# spidmx.net
KiCad netlist of a schematic drawn in EAGLE
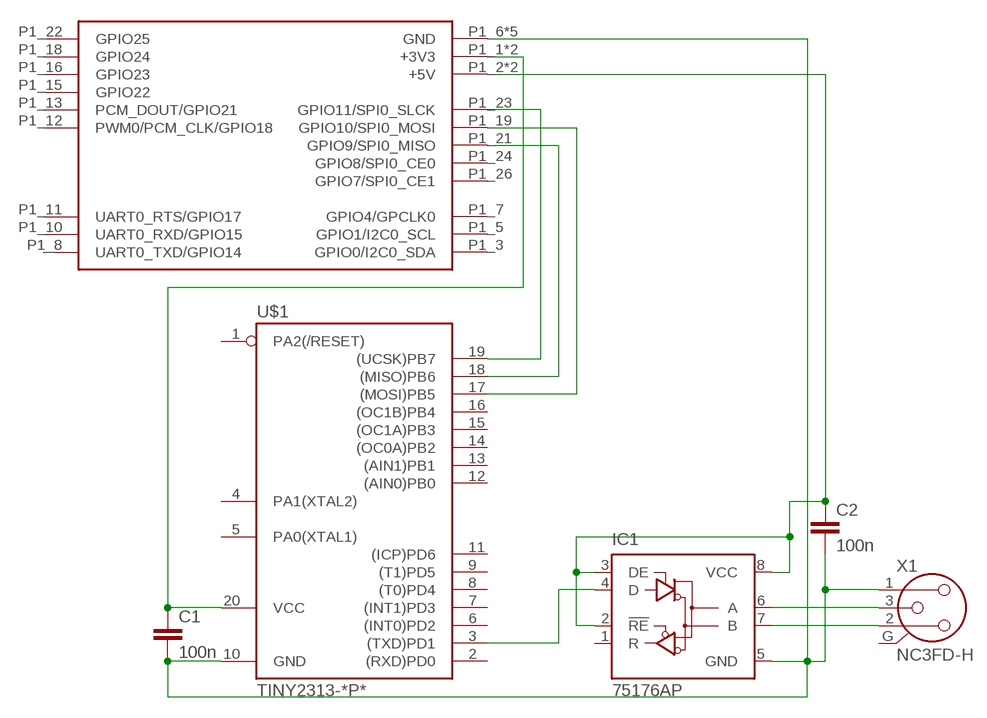
[diagram p0: schematic, sheet 1]

(export (version "E")
  (design (tool "Eeschema 10.0.6"))
  (components
    (comp (ref "C1")
      (value "100n")
      (footprint "eagle-import:C0805")
      (libsource (lib "eagle-import") (part "C-EUC0805"))
    )
    (comp (ref "C2")
      (value "100n")
      (footprint "eagle-import:C0805")
      (libsource (lib "eagle-import") (part "C-EUC0805"))
    )
    (comp (ref "IC1")
      (value "75176AP")
      (footprint "eagle-import:DIL08")
      (libsource (lib "eagle-import") (part "75176AP"))
    )
    (comp (ref "U$1")
      (value "TINY2313-*P*")
      (footprint "eagle-import:DIL20")
      (libsource (lib "eagle-import") (part "TINY2313-P"))
    )
    (comp (ref "U$2")
      (value "RPI-B-V1")
      (footprint "eagle-import:RPI-B-V1")
      (libsource (lib "eagle-import") (part "RPI-B-V1"))
    )
    (comp (ref "X1")
      (value "NC3FD-H")
      (footprint "eagle-import:NC3FD-H")
      (fields (field (name "MF") "NEUTRIK"))
      (libsource (lib "eagle-import") (part "NC3FD-H"))
    )
  )
  (nets
    (net (code "1") (name "Net-(IC1-A)") (class "Default")
      (node (ref "IC1") (pin "6") (pinfunction "A_6") (pintype "output"))
      (node (ref "X1") (pin "3") (pinfunction "3_3") (pintype "passive"))
    )
    (net (code "2") (name "Net-(IC1-B)") (class "Default")
      (node (ref "IC1") (pin "7") (pinfunction "B_7") (pintype "output"))
      (node (ref "X1") (pin "2") (pinfunction "2_2") (pintype "passive"))
    )
    (net (code "3") (name "Net-(IC1-D)") (class "Default")
      (node (ref "IC1") (pin "4") (pinfunction "D_4") (pintype "input"))
      (node (ref "U$1") (pin "3") (pinfunction "(TXD)PD1_3") (pintype "bidirectional"))
    )
    (net (code "4") (name "Net-(IC1-DE)") (class "Default")
      (node (ref "C2") (pin "1") (pinfunction "1_1") (pintype "passive"))
      (node (ref "IC1") (pin "2") (pinfunction "~{RE}_2") (pintype "input"))
      (node (ref "IC1") (pin "3") (pinfunction "DE_3") (pintype "input"))
      (node (ref "IC1") (pin "8") (pinfunction "VCC_8") (pintype "power_in"))
      (node (ref "U$2") (pin "P1_2") (pinfunction "+5V_P1_2") (pintype "power_in"))
      (node (ref "U$2") (pin "P1_4") (pinfunction "+5V_P1_4") (pintype "power_in"))
    )
    (net (code "5") (name "Net-(IC1-GND)") (class "Default")
      (node (ref "C1") (pin "2") (pinfunction "2_2") (pintype "passive"))
      (node (ref "C2") (pin "2") (pinfunction "2_2") (pintype "passive"))
      (node (ref "IC1") (pin "5") (pinfunction "GND_5") (pintype "power_in"))
      (node (ref "U$1") (pin "10") (pinfunction "GND_10") (pintype "power_in"))
      (node (ref "U$2") (pin "P1_14") (pinfunction "GND_P1_14") (pintype "power_in"))
      (node (ref "U$2") (pin "P1_20") (pinfunction "GND_P1_20") (pintype "power_in"))
      (node (ref "U$2") (pin "P1_25") (pinfunction "GND_P1_25") (pintype "power_in"))
      (node (ref "U$2") (pin "P1_6") (pinfunction "GND_P1_6") (pintype "power_in"))
      (node (ref "U$2") (pin "P1_9") (pinfunction "GND_P1_9") (pintype "power_in"))
      (node (ref "X1") (pin "1") (pinfunction "1_1") (pintype "passive"))
    )
    (net (code "6") (name "Net-(U$1-(MISO)PB6)") (class "Default")
      (node (ref "U$1") (pin "18") (pinfunction "(MISO)PB6_18") (pintype "bidirectional"))
      (node (ref "U$2") (pin "P1_21") (pinfunction "GPIO9/SPI0_MISO_P1_21") (pintype "bidirectional"))
    )
    (net (code "7") (name "Net-(U$1-(MOSI)PB5)") (class "Default")
      (node (ref "U$1") (pin "17") (pinfunction "(MOSI)PB5_17") (pintype "bidirectional"))
      (node (ref "U$2") (pin "P1_19") (pinfunction "GPIO10/SPI0_MOSI_P1_19") (pintype "bidirectional"))
    )
    (net (code "8") (name "Net-(U$1-(UCSK)PB7)") (class "Default")
      (node (ref "U$1") (pin "19") (pinfunction "(UCSK)PB7_19") (pintype "bidirectional"))
      (node (ref "U$2") (pin "P1_23") (pinfunction "GPIO11/SPI0_SLCK_P1_23") (pintype "bidirectional"))
    )
    (net (code "9") (name "Net-(U$1-VCC)") (class "Default")
      (node (ref "C1") (pin "1") (pinfunction "1_1") (pintype "passive"))
      (node (ref "U$1") (pin "20") (pinfunction "VCC_20") (pintype "power_in"))
      (node (ref "U$2") (pin "P1_1") (pinfunction "+3V3_P1_1") (pintype "power_in"))
      (node (ref "U$2") (pin "P1_17") (pinfunction "+3V3_P1_17") (pintype "power_in"))
    )
    (net (code "10") (name "unconnected-(IC1-R-Pad1)") (class "Default")
      (node (ref "IC1") (pin "1") (pinfunction "R_1") (pintype "input"))
    )
    (net (code "11") (name "unconnected-(U$1-(AIN0)PB0-Pad12)") (class "Default")
      (node (ref "U$1") (pin "12") (pinfunction "(AIN0)PB0_12") (pintype "bidirectional"))
    )
    (net (code "12") (name "unconnected-(U$1-(AIN1)PB1-Pad13)") (class "Default")
      (node (ref "U$1") (pin "13") (pinfunction "(AIN1)PB1_13") (pintype "bidirectional"))
    )
    (net (code "13") (name "unconnected-(U$1-(ICP)PD6-Pad11)") (class "Default")
      (node (ref "U$1") (pin "11") (pinfunction "(ICP)PD6_11") (pintype "bidirectional"))
    )
    (net (code "14") (name "unconnected-(U$1-(INT0)PD2-Pad6)") (class "Default")
      (node (ref "U$1") (pin "6") (pinfunction "(INT0)PD2_6") (pintype "bidirectional"))
    )
    (net (code "15") (name "unconnected-(U$1-(INT1)PD3-Pad7)") (class "Default")
      (node (ref "U$1") (pin "7") (pinfunction "(INT1)PD3_7") (pintype "bidirectional"))
    )
    (net (code "16") (name "unconnected-(U$1-(OC0A)PB2-Pad14)") (class "Default")
      (node (ref "U$1") (pin "14") (pinfunction "(OC0A)PB2_14") (pintype "bidirectional"))
    )
    (net (code "17") (name "unconnected-(U$1-(OC1A)PB3-Pad15)") (class "Default")
      (node (ref "U$1") (pin "15") (pinfunction "(OC1A)PB3_15") (pintype "bidirectional"))
    )
    (net (code "18") (name "unconnected-(U$1-(OC1B)PB4-Pad16)") (class "Default")
      (node (ref "U$1") (pin "16") (pinfunction "(OC1B)PB4_16") (pintype "bidirectional"))
    )
    (net (code "19") (name "unconnected-(U$1-(RXD)PD0-Pad2)") (class "Default")
      (node (ref "U$1") (pin "2") (pinfunction "(RXD)PD0_2") (pintype "bidirectional"))
    )
    (net (code "20") (name "unconnected-(U$1-(T0)PD4-Pad8)") (class "Default")
      (node (ref "U$1") (pin "8") (pinfunction "(T0)PD4_8") (pintype "bidirectional"))
    )
    (net (code "21") (name "unconnected-(U$1-(T1)PD5-Pad9)") (class "Default")
      (node (ref "U$1") (pin "9") (pinfunction "(T1)PD5_9") (pintype "bidirectional"))
    )
    (net (code "22") (name "unconnected-(U$1-PA0(XTAL1)-Pad5)") (class "Default")
      (node (ref "U$1") (pin "5") (pinfunction "PA0(XTAL1)_5") (pintype "bidirectional"))
    )
    (net (code "23") (name "unconnected-(U$1-PA1(XTAL2)-Pad4)") (class "Default")
      (node (ref "U$1") (pin "4") (pinfunction "PA1(XTAL2)_4") (pintype "bidirectional"))
    )
    (net (code "24") (name "unconnected-(U$1-PA2({slash}RESET)-Pad1)") (class "Default")
      (node (ref "U$1") (pin "1") (pinfunction "PA2(/RESET)_1") (pintype "input"))
    )
    (net (code "25") (name "unconnected-(U$2-GPIO0{slash}I2C0_SDA-PadP1_3)") (class "Default")
      (node (ref "U$2") (pin "P1_3") (pinfunction "GPIO0/I2C0_SDA_P1_3") (pintype "bidirectional"))
    )
    (net (code "26") (name "unconnected-(U$2-GPIO1{slash}I2C0_SCL-PadP1_5)") (class "Default")
      (node (ref "U$2") (pin "P1_5") (pinfunction "GPIO1/I2C0_SCL_P1_5") (pintype "bidirectional"))
    )
    (net (code "27") (name "unconnected-(U$2-GPIO4{slash}GPCLK0-PadP1_7)") (class "Default")
      (node (ref "U$2") (pin "P1_7") (pinfunction "GPIO4/GPCLK0_P1_7") (pintype "bidirectional"))
    )
    (net (code "28") (name "unconnected-(U$2-GPIO7{slash}SPI0_CE1-PadP1_26)") (class "Default")
      (node (ref "U$2") (pin "P1_26") (pinfunction "GPIO7/SPI0_CE1_P1_26") (pintype "bidirectional"))
    )
    (net (code "29") (name "unconnected-(U$2-GPIO8{slash}SPI0_CE0-PadP1_24)") (class "Default")
      (node (ref "U$2") (pin "P1_24") (pinfunction "GPIO8/SPI0_CE0_P1_24") (pintype "bidirectional"))
    )
    (net (code "30") (name "unconnected-(U$2-GPIO22-PadP1_15)") (class "Default")
      (node (ref "U$2") (pin "P1_15") (pinfunction "GPIO22_P1_15") (pintype "bidirectional"))
    )
    (net (code "31") (name "unconnected-(U$2-GPIO23-PadP1_16)") (class "Default")
      (node (ref "U$2") (pin "P1_16") (pinfunction "GPIO23_P1_16") (pintype "bidirectional"))
    )
    (net (code "32") (name "unconnected-(U$2-GPIO24-PadP1_18)") (class "Default")
      (node (ref "U$2") (pin "P1_18") (pinfunction "GPIO24_P1_18") (pintype "bidirectional"))
    )
    (net (code "33") (name "unconnected-(U$2-GPIO25-PadP1_22)") (class "Default")
      (node (ref "U$2") (pin "P1_22") (pinfunction "GPIO25_P1_22") (pintype "bidirectional"))
    )
    (net (code "34") (name "unconnected-(U$2-PCM_DOUT{slash}GPIO21-PadP1_13)") (class "Default")
      (node (ref "U$2") (pin "P1_13") (pinfunction "PCM_DOUT/GPIO21_P1_13") (pintype "bidirectional"))
    )
    (net (code "35") (name "unconnected-(U$2-PWM0{slash}PCM_CLK{slash}GPIO18-PadP1_12)") (class "Default")
      (node (ref "U$2") (pin "P1_12") (pinfunction "PWM0/PCM_CLK/GPIO18_P1_12") (pintype "bidirectional"))
    )
    (net (code "36") (name "unconnected-(U$2-UART0_RTS{slash}GPIO17-PadP1_11)") (class "Default")
      (node (ref "U$2") (pin "P1_11") (pinfunction "UART0_RTS/GPIO17_P1_11") (pintype "bidirectional"))
    )
    (net (code "37") (name "unconnected-(U$2-UART0_RXD{slash}GPIO15-PadP1_10)") (class "Default")
      (node (ref "U$2") (pin "P1_10") (pinfunction "UART0_RXD/GPIO15_P1_10") (pintype "bidirectional"))
    )
    (net (code "38") (name "unconnected-(U$2-UART0_TXD{slash}GPIO14-PadP1_8)") (class "Default")
      (node (ref "U$2") (pin "P1_8") (pinfunction "UART0_TXD/GPIO14_P1_8") (pintype "bidirectional"))
    )
    (net (code "39") (name "unconnected-(X1-PadG)") (class "Default")
      (node (ref "X1") (pin "G") (pinfunction "G_G") (pintype "passive"))
    )
  )
)
